# converter.net
KiCad netlist of a schematic drawn in EAGLE
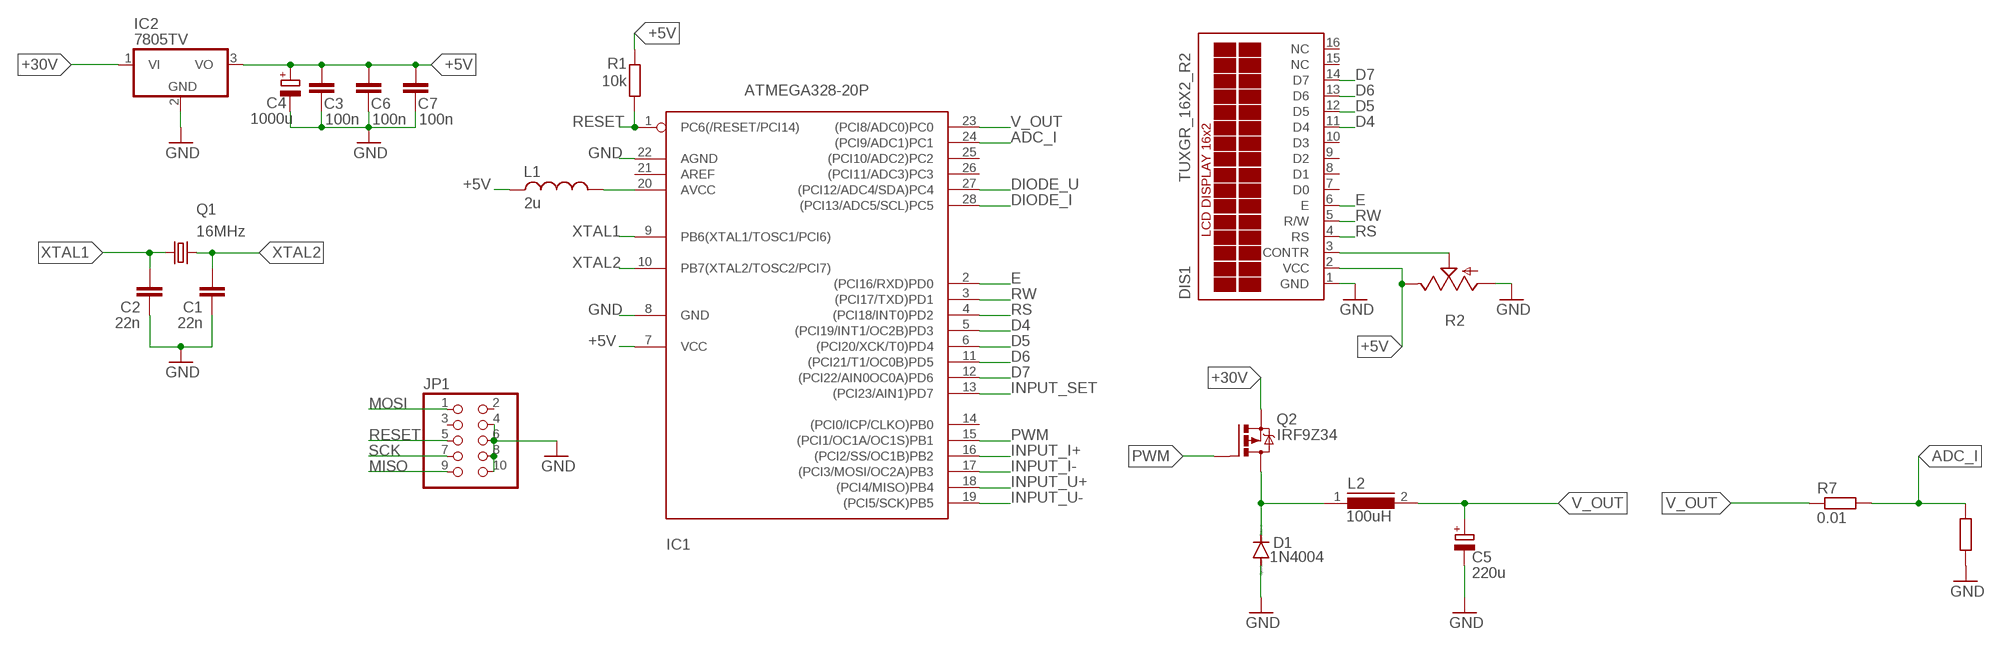
[diagram p0: schematic, sheet 1]

(export (version "E")
  (design (tool "Eeschema 10.0.6"))
  (components
    (comp (ref "C1")
      (value "22n")
      (footprint "eagle-import:C2.5-3")
      (libsource (lib "eagle-import") (part "C2,5-3"))
    )
    (comp (ref "C2")
      (value "22n")
      (footprint "eagle-import:C2.5-3")
      (libsource (lib "eagle-import") (part "C2,5-3"))
    )
    (comp (ref "C3")
      (value "100n")
      (footprint "eagle-import:C2.5-3")
      (libsource (lib "eagle-import") (part "C2,5-3"))
    )
    (comp (ref "C4")
      (value "1000u")
      (footprint "eagle-import:E2,5-7")
      (libsource (lib "eagle-import") (part "CPOL-EUE2.5-7"))
    )
    (comp (ref "C5")
      (value "220u")
      (footprint "eagle-import:E2,5-7")
      (libsource (lib "eagle-import") (part "CPOL-EUE2.5-7"))
    )
    (comp (ref "C6")
      (value "100n")
      (footprint "eagle-import:C2.5-3")
      (libsource (lib "eagle-import") (part "C2,5-3"))
    )
    (comp (ref "C7")
      (value "100n")
      (footprint "eagle-import:C2.5-3")
      (libsource (lib "eagle-import") (part "C2,5-3"))
    )
    (comp (ref "D1")
      (value "1N4004")
      (footprint "eagle-import:DO41-10")
      (libsource (lib "eagle-import") (part "1N4004"))
    )
    (comp (ref "DIS1")
      (value "TUXGR_16X2_R2")
      (footprint "eagle-import:TUXGR_16X2_R2")
      (libsource (lib "eagle-import") (part "TUXGR_16X2_R2"))
    )
    (comp (ref "IC1")
      (value "ATMEGA328-20P")
      (footprint "eagle-import:DIL28-3")
      (libsource (lib "eagle-import") (part "ATMEGA328P-20"))
    )
    (comp (ref "IC2")
      (value "7805TV")
      (footprint "eagle-import:TO220V")
      (libsource (lib "eagle-import") (part "78TV05"))
    )
    (comp (ref "JP1")
      (value "PINHD-2X5")
      (footprint "eagle-import:2X05")
      (libsource (lib "eagle-import") (part "PINHD-2X5"))
    )
    (comp (ref "L1")
      (value "2u")
      (footprint "eagle-import:0204_7")
      (libsource (lib "eagle-import") (part "L-US0204/7"))
    )
    (comp (ref "L2")
      (value "100uH")
      (footprint "eagle-import:ED26")
      (libsource (lib "eagle-import") (part "ED26"))
    )
    (comp (ref "Q1")
      (value "16MHz")
      (footprint "eagle-import:HC49_S")
      (libsource (lib "eagle-import") (part "CRYSTALHC49S"))
    )
    (comp (ref "Q2")
      (value "IRF9Z34")
      (footprint "eagle-import:TO220BH")
      (libsource (lib "eagle-import") (part "IRF4905"))
    )
    (comp (ref "R1")
      (value "10k")
      (footprint "eagle-import:0204_7")
      (libsource (lib "eagle-import") (part "resistor_348_R-EU_0204/7"))
    )
    (comp (ref "R2")
      (value "TRIM_US-LI15")
      (footprint "eagle-import:LI15")
      (libsource (lib "eagle-import") (part "TRIM_US-LI15"))
    )
    (comp (ref "R7")
      (value "0.01")
      (footprint "eagle-import:0207_10")
      (libsource (lib "eagle-import") (part "R-EU_0207/10"))
    )
  )
  (nets
    (net (code "1") (name "+5V") (class "Default")
      (node (ref "C3") (pin "2") (pinfunction "2_2") (pintype "passive"))
      (node (ref "C4") (pin "+") (pinfunction "+_+") (pintype "passive"))
      (node (ref "C6") (pin "2") (pinfunction "2_2") (pintype "passive"))
      (node (ref "C7") (pin "2") (pinfunction "2_2") (pintype "passive"))
      (node (ref "DIS1") (pin "2") (pinfunction "VCC_2") (pintype "power_in"))
      (node (ref "IC1") (pin "7") (pinfunction "VCC_7") (pintype "bidirectional"))
      (node (ref "IC2") (pin "3") (pinfunction "VO_3") (pintype "passive"))
      (node (ref "L1") (pin "1") (pinfunction "1_1") (pintype "passive"))
      (node (ref "R1") (pin "2") (pinfunction "2_2") (pintype "passive"))
      (node (ref "R2") (pin "E") (pinfunction "E_E") (pintype "passive"))
    )
    (net (code "2") (name "+30V") (class "Default")
      (node (ref "IC2") (pin "1") (pinfunction "VI_1") (pintype "input"))
      (node (ref "Q2") (pin "S") (pinfunction "S_S") (pintype "passive"))
    )
    (net (code "3") (name "/D4") (class "Default")
      (node (ref "DIS1") (pin "11") (pinfunction "D4_11") (pintype "input"))
      (node (ref "IC1") (pin "5") (pinfunction "(PCI19/INT1/OC2B)PD3_5") (pintype "bidirectional"))
    )
    (net (code "4") (name "/D5") (class "Default")
      (node (ref "DIS1") (pin "12") (pinfunction "D5_12") (pintype "input"))
      (node (ref "IC1") (pin "6") (pinfunction "(PCI20/XCK/T0)PD4_6") (pintype "bidirectional"))
    )
    (net (code "5") (name "/D6") (class "Default")
      (node (ref "DIS1") (pin "13") (pinfunction "D6_13") (pintype "input"))
      (node (ref "IC1") (pin "11") (pinfunction "(PCI21/T1/OC0B)PD5_11") (pintype "bidirectional"))
    )
    (net (code "6") (name "/D7") (class "Default")
      (node (ref "DIS1") (pin "14") (pinfunction "D7_14") (pintype "input"))
      (node (ref "IC1") (pin "12") (pinfunction "(PCI22/AIN0OC0A)PD6_12") (pintype "bidirectional"))
    )
    (net (code "7") (name "/DIODE_I") (class "Default")
      (node (ref "IC1") (pin "28") (pinfunction "(PCI13/ADC5/SCL)PC5_28") (pintype "bidirectional"))
    )
    (net (code "8") (name "/DIODE_U") (class "Default")
      (node (ref "IC1") (pin "27") (pinfunction "(PCI12/ADC4/SDA)PC4_27") (pintype "bidirectional"))
    )
    (net (code "9") (name "/E") (class "Default")
      (node (ref "DIS1") (pin "6") (pinfunction "E_6") (pintype "input"))
      (node (ref "IC1") (pin "2") (pinfunction "(PCI16/RXD)PD0_2") (pintype "bidirectional"))
    )
    (net (code "10") (name "/INPUT_I+") (class "Default")
      (node (ref "IC1") (pin "16") (pinfunction "(PCI2/SS/OC1B)PB2_16") (pintype "bidirectional"))
    )
    (net (code "11") (name "/INPUT_I-") (class "Default")
      (node (ref "IC1") (pin "17") (pinfunction "(PCI3/MOSI/OC2A)PB3_17") (pintype "bidirectional"))
    )
    (net (code "12") (name "/INPUT_SET") (class "Default")
      (node (ref "IC1") (pin "13") (pinfunction "(PCI23/AIN1)PD7_13") (pintype "bidirectional"))
    )
    (net (code "13") (name "/INPUT_U+") (class "Default")
      (node (ref "IC1") (pin "18") (pinfunction "(PCI4/MISO)PB4_18") (pintype "bidirectional"))
    )
    (net (code "14") (name "/INPUT_U-") (class "Default")
      (node (ref "IC1") (pin "19") (pinfunction "(PCI5/SCK)PB5_19") (pintype "bidirectional"))
    )
    (net (code "15") (name "/MISO") (class "Default")
      (node (ref "JP1") (pin "9") (pinfunction "9_9") (pintype "passive"))
    )
    (net (code "16") (name "/MOSI") (class "Default")
      (node (ref "JP1") (pin "1") (pinfunction "1_1") (pintype "passive"))
    )
    (net (code "17") (name "/RESET") (class "Default")
      (node (ref "IC1") (pin "1") (pinfunction "PC6(/RESET/PCI14)_1") (pintype "bidirectional"))
      (node (ref "JP1") (pin "5") (pinfunction "5_5") (pintype "passive"))
      (node (ref "R1") (pin "1") (pinfunction "1_1") (pintype "passive"))
    )
    (net (code "18") (name "/RS") (class "Default")
      (node (ref "DIS1") (pin "4") (pinfunction "RS_4") (pintype "input"))
      (node (ref "IC1") (pin "4") (pinfunction "(PCI18/INT0)PD2_4") (pintype "bidirectional"))
    )
    (net (code "19") (name "/RW") (class "Default")
      (node (ref "DIS1") (pin "5") (pinfunction "R/W_5") (pintype "input"))
      (node (ref "IC1") (pin "3") (pinfunction "(PCI17/TXD)PD1_3") (pintype "bidirectional"))
    )
    (net (code "20") (name "/SCK") (class "Default")
      (node (ref "JP1") (pin "7") (pinfunction "7_7") (pintype "passive"))
    )
    (net (code "21") (name "ADC_I") (class "Default")
      (node (ref "IC1") (pin "24") (pinfunction "(PCI9/ADC1)PC1_24") (pintype "bidirectional"))
      (node (ref "R7") (pin "2") (pinfunction "2_2") (pintype "passive"))
    )
    (net (code "22") (name "GND") (class "Default")
      (node (ref "C1") (pin "1") (pinfunction "1_1") (pintype "passive"))
      (node (ref "C2") (pin "1") (pinfunction "1_1") (pintype "passive"))
      (node (ref "C3") (pin "1") (pinfunction "1_1") (pintype "passive"))
      (node (ref "C4") (pin "-") (pinfunction "-_-") (pintype "passive"))
      (node (ref "C5") (pin "-") (pinfunction "-_-") (pintype "passive"))
      (node (ref "C6") (pin "1") (pinfunction "1_1") (pintype "passive"))
      (node (ref "C7") (pin "1") (pinfunction "1_1") (pintype "passive"))
      (node (ref "D1") (pin "A") (pinfunction "A_A") (pintype "passive"))
      (node (ref "DIS1") (pin "1") (pinfunction "GND_1") (pintype "power_in"))
      (node (ref "IC1") (pin "22") (pinfunction "AGND_22") (pintype "bidirectional"))
      (node (ref "IC1") (pin "8") (pinfunction "GND_8") (pintype "bidirectional"))
      (node (ref "IC2") (pin "2") (pinfunction "GND_2") (pintype "passive"))
      (node (ref "JP1") (pin "10") (pinfunction "10_10") (pintype "passive"))
      (node (ref "JP1") (pin "4") (pinfunction "4_4") (pintype "passive"))
      (node (ref "JP1") (pin "6") (pinfunction "6_6") (pintype "passive"))
      (node (ref "JP1") (pin "8") (pinfunction "8_8") (pintype "passive"))
      (node (ref "R2") (pin "A") (pinfunction "A_A") (pintype "passive"))
    )
    (net (code "23") (name "Net-(D1-PadC)") (class "Default")
      (node (ref "D1") (pin "C") (pinfunction "C_C") (pintype "passive"))
      (node (ref "L2") (pin "1") (pinfunction "1_1") (pintype "passive"))
      (node (ref "Q2") (pin "D") (pinfunction "D_D") (pintype "passive"))
    )
    (net (code "24") (name "Net-(DIS1-CONTR)") (class "Default")
      (node (ref "DIS1") (pin "3") (pinfunction "CONTR_3") (pintype "input"))
      (node (ref "R2") (pin "S") (pinfunction "S_S") (pintype "passive"))
    )
    (net (code "25") (name "Net-(IC1-AVCC)") (class "Default")
      (node (ref "IC1") (pin "20") (pinfunction "AVCC_20") (pintype "bidirectional"))
      (node (ref "L1") (pin "2") (pinfunction "2_2") (pintype "passive"))
    )
    (net (code "26") (name "PWM") (class "Default")
      (node (ref "IC1") (pin "15") (pinfunction "(PCI1/OC1A/OC1S)PB1_15") (pintype "bidirectional"))
      (node (ref "Q2") (pin "G") (pinfunction "G_G") (pintype "passive"))
    )
    (net (code "27") (name "V_OUT") (class "Default")
      (node (ref "C5") (pin "+") (pinfunction "+_+") (pintype "passive"))
      (node (ref "IC1") (pin "23") (pinfunction "(PCI8/ADC0)PC0_23") (pintype "bidirectional"))
      (node (ref "L2") (pin "2") (pinfunction "2_2") (pintype "passive"))
      (node (ref "R7") (pin "1") (pinfunction "1_1") (pintype "passive"))
    )
    (net (code "28") (name "XTAL1") (class "Default")
      (node (ref "C2") (pin "2") (pinfunction "2_2") (pintype "passive"))
      (node (ref "IC1") (pin "9") (pinfunction "PB6(XTAL1/TOSC1/PCI6)_9") (pintype "bidirectional"))
      (node (ref "Q1") (pin "2") (pinfunction "2_2") (pintype "passive"))
    )
    (net (code "29") (name "XTAL2") (class "Default")
      (node (ref "C1") (pin "2") (pinfunction "2_2") (pintype "passive"))
      (node (ref "IC1") (pin "10") (pinfunction "PB7(XTAL2/TOSC2/PCI7)_10") (pintype "bidirectional"))
      (node (ref "Q1") (pin "1") (pinfunction "1_1") (pintype "passive"))
    )
    (net (code "30") (name "unconnected-(DIS1-D0-Pad7)") (class "Default")
      (node (ref "DIS1") (pin "7") (pinfunction "D0_7") (pintype "input"))
    )
    (net (code "31") (name "unconnected-(DIS1-D1-Pad8)") (class "Default")
      (node (ref "DIS1") (pin "8") (pinfunction "D1_8") (pintype "input"))
    )
    (net (code "32") (name "unconnected-(DIS1-D2-Pad9)") (class "Default")
      (node (ref "DIS1") (pin "9") (pinfunction "D2_9") (pintype "input"))
    )
    (net (code "33") (name "unconnected-(DIS1-D3-Pad10)") (class "Default")
      (node (ref "DIS1") (pin "10") (pinfunction "D3_10") (pintype "input"))
    )
    (net (code "34") (name "unconnected-(DIS1-NC-Pad15)") (class "Default")
      (node (ref "DIS1") (pin "15") (pinfunction "NC_15") (pintype "no_connect"))
    )
    (net (code "35") (name "unconnected-(DIS1-NC-Pad16)") (class "Default")
      (node (ref "DIS1") (pin "16") (pinfunction "NC_16") (pintype "no_connect"))
    )
    (net (code "36") (name "unconnected-(IC1-(PCI0{slash}ICP{slash}CLKO)PB0-Pad14)") (class "Default")
      (node (ref "IC1") (pin "14") (pinfunction "(PCI0/ICP/CLKO)PB0_14") (pintype "bidirectional"))
    )
    (net (code "37") (name "unconnected-(IC1-(PCI10{slash}ADC2)PC2-Pad25)") (class "Default")
      (node (ref "IC1") (pin "25") (pinfunction "(PCI10/ADC2)PC2_25") (pintype "bidirectional"))
    )
    (net (code "38") (name "unconnected-(IC1-(PCI11{slash}ADC3)PC3-Pad26)") (class "Default")
      (node (ref "IC1") (pin "26") (pinfunction "(PCI11/ADC3)PC3_26") (pintype "bidirectional"))
    )
    (net (code "39") (name "unconnected-(IC1-AREF-Pad21)") (class "Default")
      (node (ref "IC1") (pin "21") (pinfunction "AREF_21") (pintype "bidirectional"))
    )
    (net (code "40") (name "unconnected-(JP1-Pad2)") (class "Default")
      (node (ref "JP1") (pin "2") (pinfunction "2_2") (pintype "passive"))
    )
    (net (code "41") (name "unconnected-(JP1-Pad3)") (class "Default")
      (node (ref "JP1") (pin "3") (pinfunction "3_3") (pintype "passive"))
    )
  )
)
